# Toygether_Sch.net
KiCad netlist of a schematic drawn in Altium Designer
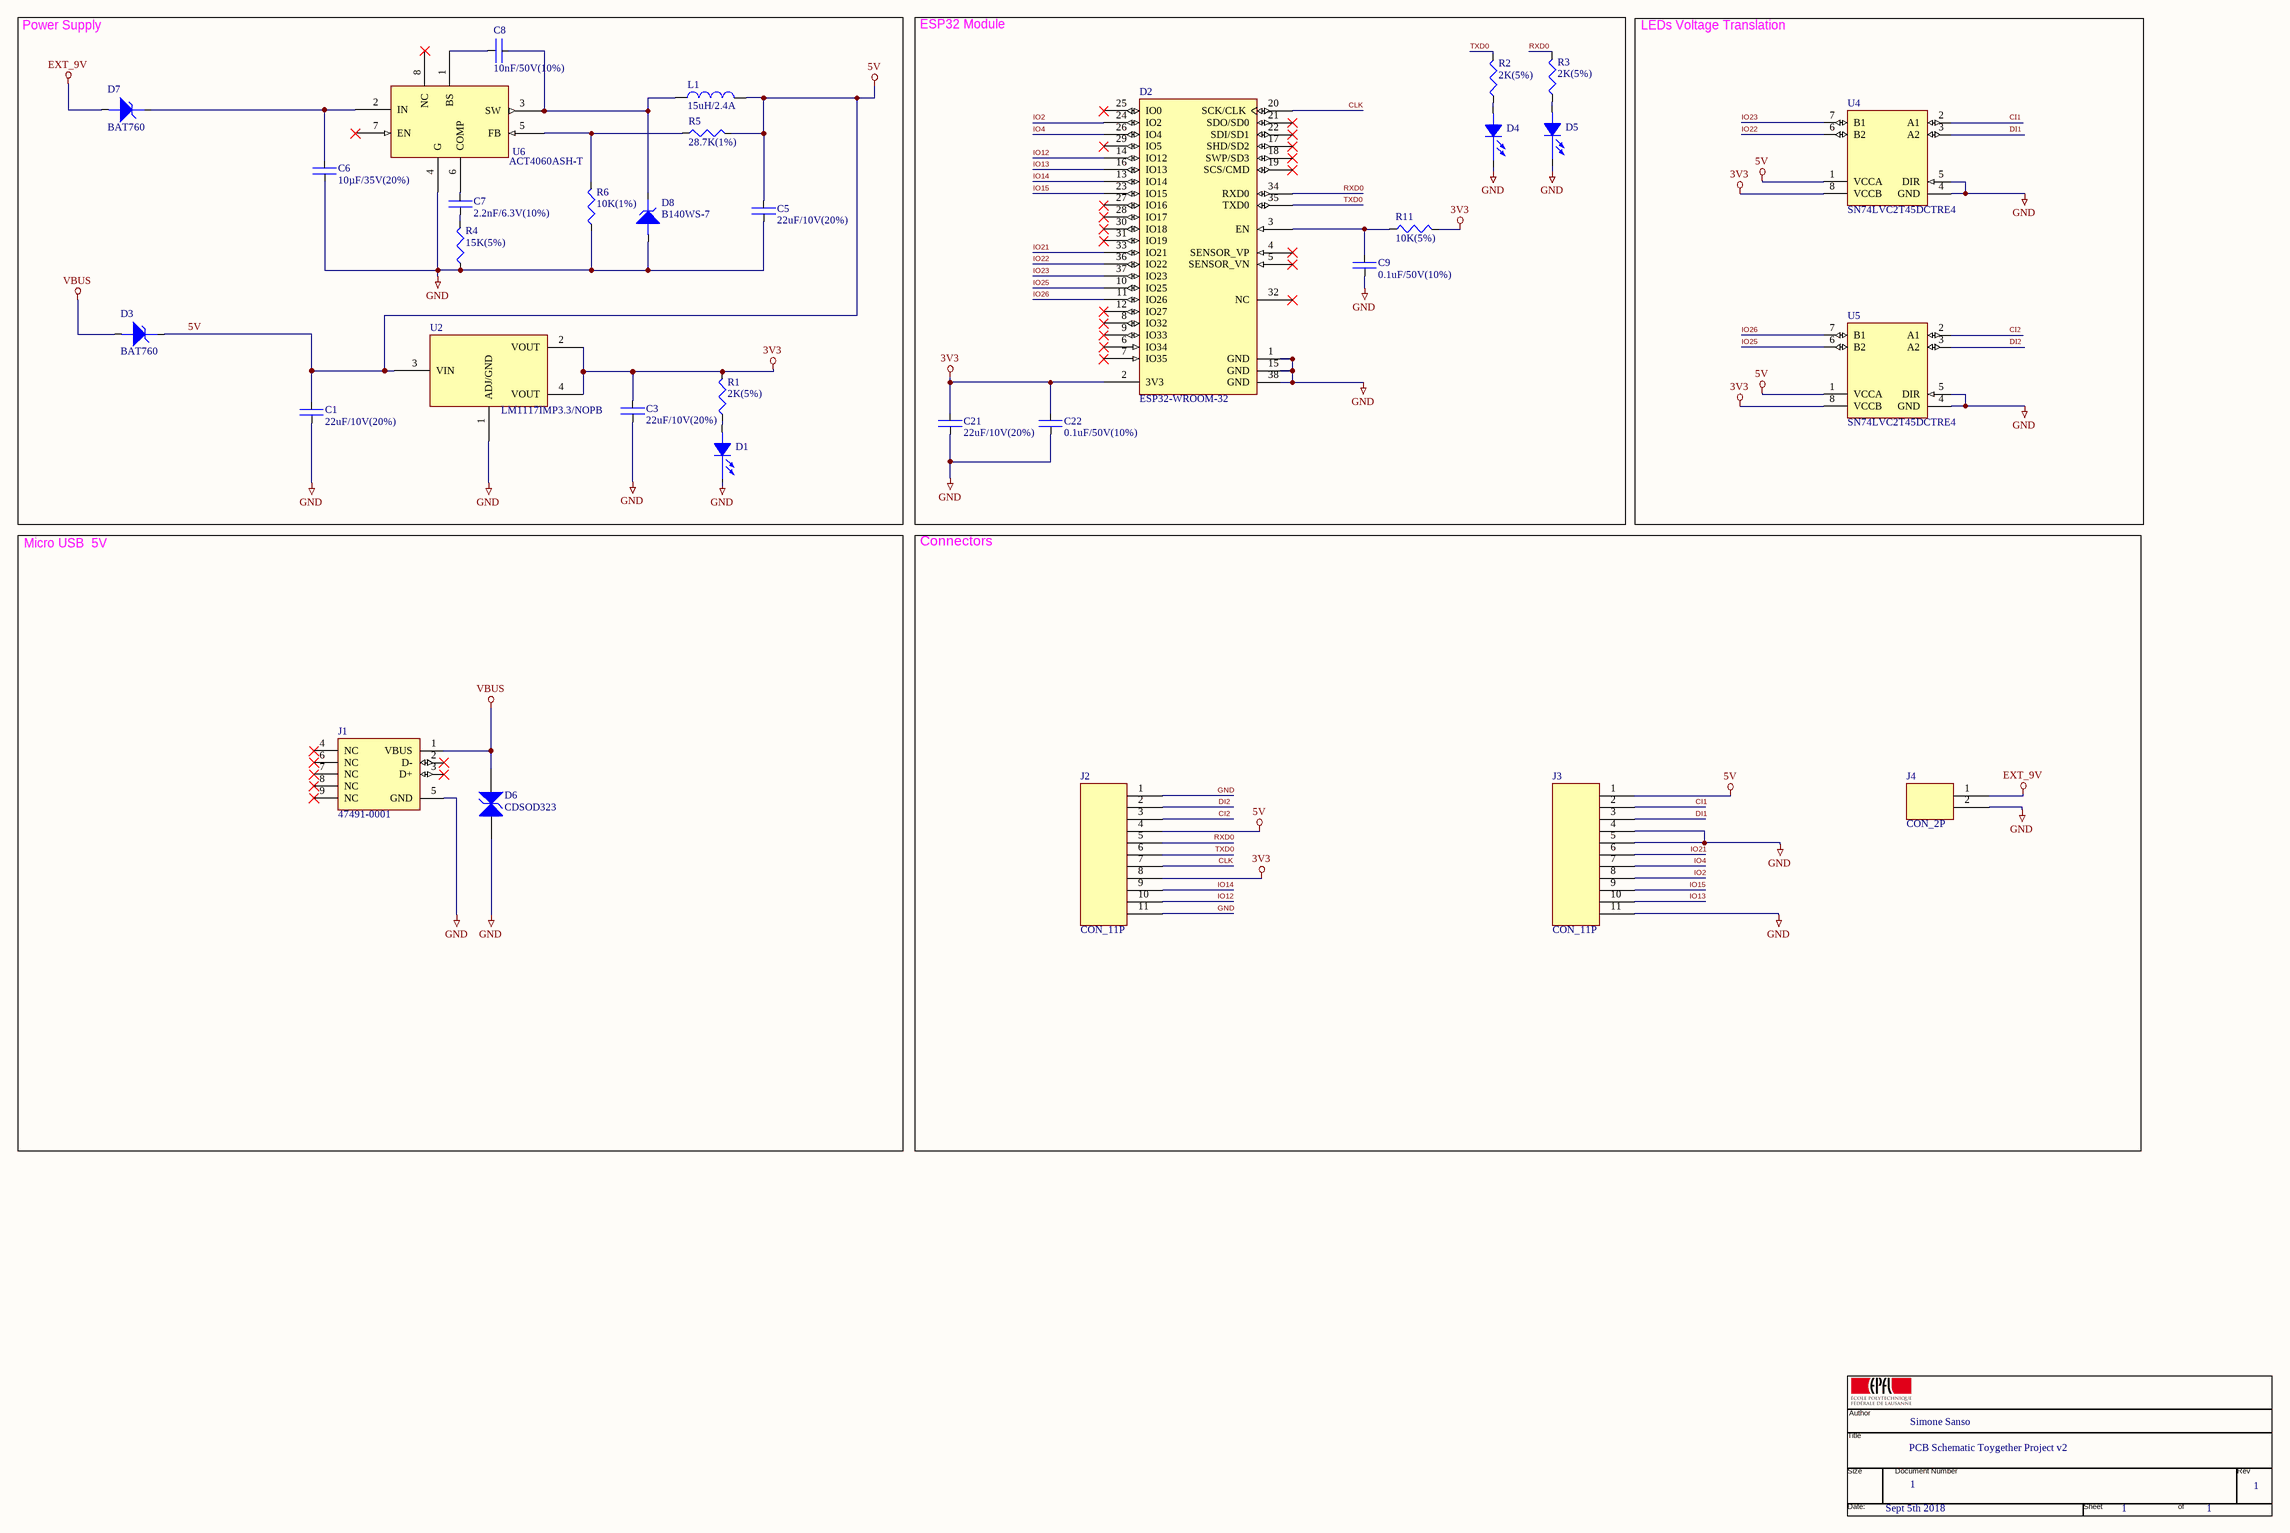
[diagram p0: Toygether_Sch.SchDoc]

(export (version "E")
  (design (tool "Eeschema 10.0.6"))
  (components
    (comp (ref "C1")
      (value "22uF/10V(20%)")
      (footprint "CAPC0603")
      (description "GRM188R61A226ME15D-22uF/10V(20%)")
      (libsource (lib "NAPaC_Schlib") (part "CAP-22uF/10V(20%)"))
    )
    (comp (ref "C3")
      (value "22uF/10V(20%)")
      (footprint "CAPC0603")
      (description "GRM188R61A226ME15D-22uF/10V(20%)")
      (libsource (lib "NAPaC_Schlib") (part "CAP-22uF/10V(20%)"))
    )
    (comp (ref "C5")
      (value "22uF/10V(20%)")
      (footprint "CAPC0603")
      (description "GRM188R61A226ME15D-22uF/10V(20%)")
      (libsource (lib "NAPaC_Schlib") (part "CAP-22uF/10V(20%)"))
    )
    (comp (ref "C6")
      (value "10µF/35V(20%)")
      (footprint "CAPC0603")
      (description "C0603C106M8PACTU")
      (libsource (lib "NAPaC_Schlib") (part "CAP-10µF/35V(20%)"))
    )
    (comp (ref "C7")
      (value "2.2nF/6.3V(10%)")
      (footprint "CAPC0603")
      (description "C0603X7R0J222K030BA")
      (libsource (lib "NAPaC_Schlib") (part "CAP-2.2nF/6.3V(10%)"))
    )
    (comp (ref "C8")
      (value "10nF/50V(10%)")
      (footprint "CAPC0603")
      (description "C1608X7R1H103K080AE")
      (libsource (lib "NAPaC_Schlib") (part "CAP-10nF/50V(10%)"))
    )
    (comp (ref "C9")
      (value "0.1uF/50V(10%)")
      (footprint "CAPC0603")
      (description "GRM188R71H104KA93D-0.1uF/50V(10%)")
      (libsource (lib "NAPaC_Schlib") (part "CAP-0.1uF/50V(10%)"))
    )
    (comp (ref "C21")
      (value "22uF/10V(20%)")
      (footprint "CAPC0603")
      (description "GRM188R61A226ME15D-22uF/10V(20%)")
      (libsource (lib "NAPaC_Schlib") (part "CAP-22uF/10V(20%)"))
    )
    (comp (ref "C22")
      (value "0.1uF/50V(10%)")
      (footprint "CAPC0603")
      (description "GRM188R71H104KA93D-0.1uF/50V(10%)")
      (libsource (lib "NAPaC_Schlib") (part "CAP-0.1uF/50V(10%)"))
    )
    (comp (ref "D1")
      (value "SML-D12U1WT86")
      (footprint "SML-D12U1WT86")
      (description "SML-D12U1WT86-2.2V-20mA")
      (libsource (lib "NAPaC_Schlib") (part "RED_LED"))
    )
    (comp (ref "D2")
      (value "ESP32-WROOM-32")
      (footprint "OLMX-ESP-WROOM-32")
      (libsource (lib "Toygether_Schlib") (part "ESP-WROOM-32"))
    )
    (comp (ref "D3")
      (value "BAT760")
      (footprint "SOD-323-SCHOTTKY_DIODE-30V/0.5A")
      (description "BAT760-7-Schottky Diodes & Rectifiers 0.5A 30V LF")
      (libsource (lib "Toygether_Schlib") (part "SCHOTTKY_DIODE-30V/0.5A"))
    )
    (comp (ref "D4")
      (value "SML-D12U1WT86")
      (footprint "SML-D12U1WT86")
      (description "SML-D12U1WT86-2.2V-20mA")
      (libsource (lib "NAPaC_Schlib") (part "RED_LED"))
    )
    (comp (ref "D5")
      (value "SML-D12U1WT86")
      (footprint "SML-D12U1WT86")
      (description "SML-D12U1WT86-2.2V-20mA")
      (libsource (lib "NAPaC_Schlib") (part "RED_LED"))
    )
    (comp (ref "D6")
      (value "CDSOD323")
      (footprint "SOD-323-SCHOTTKY_DIODE-30V/0.5A")
      (description "CDSOD323-T05LC - ESD Suppressors / TVS Diodes Bidirectional Ultra Low Cap")
      (libsource (lib "Toygether_Schlib") (part "BIDIRECTIONAL_DIODE"))
    )
    (comp (ref "D7")
      (value "BAT760")
      (footprint "SOD-323-SCHOTTKY_DIODE-30V/0.5A")
      (description "BAT760-7-Schottky Diodes & Rectifiers 0.5A 30V LF")
      (libsource (lib "Toygether_Schlib") (part "SCHOTTKY_DIODE-30V/0.5A"))
    )
    (comp (ref "D8")
      (value "B140WS-7")
      (footprint "SOD-323-SCHOTTKY_DIODE-40V/1A")
      (description "Diode Schottky 40V 1A 2-Pin SOD-323 T/R")
      (libsource (lib "NAPaC_Schlib") (part "SCHOTTKY_DIODE-40V/3A"))
    )
    (comp (ref "J1")
      (value "47491-0001")
      (footprint "USB-MICRO-B_V")
      (description "USB Connectors MICRO USB B RECPT MIDDLE MNT ASSY")
      (libsource (lib "Toygether_Schlib") (part "USB_CON8"))
    )
    (comp (ref "J2")
      (value "CON_11P")
      (footprint "PINS_HEADER-11")
      (description "11 Positions Header, Breakaway Connector 0.100\" (2.54mm) Through Hole Tin")
      (libsource (lib "Toygether_Schlib") (part "PINS_HEADER_11"))
    )
    (comp (ref "J3")
      (value "CON_11P")
      (footprint "PINS_HEADER-11")
      (description "11 Positions Header, Breakaway Connector 0.100\" (2.54mm) Through Hole Tin")
      (libsource (lib "Toygether_Schlib") (part "PINS_HEADER_11"))
    )
    (comp (ref "J4")
      (value "CON_2P")
      (footprint "PINS_ALIM-2")
      (description "2 Positions Header, Breakaway Connector 0.100\" (2.54mm) Through Hole Tin")
      (libsource (lib "NAPaC_Schlib") (part "PIN_ALIM"))
    )
    (comp (ref "L1")
      (value "15uH/2.4A")
      (footprint "NRS8040-SELF-15uH/2.4A")
      (description "NRS8040T150MJGJ")
      (libsource (lib "NAPaC_Schlib") (part "SELF-15uH/2.4A"))
    )
    (comp (ref "R1")
      (value "2K(5%)")
      (footprint "RC0402")
      (description "RC0402JR-072KL")
      (libsource (lib "NAPaC_Schlib") (part "RESISTOR-2K(5%)"))
    )
    (comp (ref "R2")
      (value "2K(5%)")
      (footprint "RC0402")
      (description "RC0402JR-072KL")
      (libsource (lib "NAPaC_Schlib") (part "RESISTOR-2K(5%)"))
    )
    (comp (ref "R3")
      (value "2K(5%)")
      (footprint "RC0402")
      (description "RC0402JR-072KL")
      (libsource (lib "NAPaC_Schlib") (part "RESISTOR-2K(5%)"))
    )
    (comp (ref "R4")
      (value "15K(5%)")
      (footprint "RC0402")
      (description "RC0402JR-0715KL")
      (libsource (lib "NAPaC_Schlib") (part "RESISTOR-15K(5%)"))
    )
    (comp (ref "R5")
      (value "28.7K(1%)")
      (footprint "RC0402")
      (description "RC0402JR-072K7L")
      (libsource (lib "NAPaC_Schlib") (part "RESISTOR-28.7K(1%)"))
    )
    (comp (ref "R6")
      (value "10K(1%)")
      (footprint "RC0402")
      (description "RC0402F103CS")
      (libsource (lib "NAPaC_Schlib") (part "RESISTOR-10K(1%)"))
    )
    (comp (ref "R11")
      (value "10K(5%)")
      (footprint "RC0402")
      (description "RC0402JR-0710KL")
      (libsource (lib "NAPaC_Schlib") (part "RESISTOR-10K(5%)"))
    )
    (comp (ref "T") (value "TITLE_BLOCK") (libsource (lib "Toygether_Schlib") (part "TITLE_BLOCK")))
    (comp (ref "U2")
      (value "LM1117IMP3.3/NOPB")
      (footprint "LM1117")
      (libsource (lib "NAPaC_Schlib") (part "LM1117-3.3"))
    )
    (comp (ref "U4")
      (value "SN74LVC2T45DCTRE4")
      (footprint "VOLTAGE_TRANSLATOR_3.3-5V")
      (description "Translation - Voltage Levels DUAL-BIT DUAL SUPPLY TRANSCEIVER")
      (libsource (lib "NAPaC_Schlib") (part "VOLTAGE_TRANSLATOR_3.3-5V"))
    )
    (comp (ref "U5")
      (value "SN74LVC2T45DCTRE4")
      (footprint "VOLTAGE_TRANSLATOR_3.3-5V")
      (description "Translation - Voltage Levels DUAL-BIT DUAL SUPPLY TRANSCEIVER")
      (libsource (lib "NAPaC_Schlib") (part "VOLTAGE_TRANSLATOR_3.3-5V"))
    )
    (comp (ref "U6")
      (value "ACT4060ASH-T")
      (footprint "SWITCHING_VOLTAGE_REGULATOR")
      (libsource (lib "NAPaC_Schlib") (part "SWITCHING_VOLTAGE_REGULATOR"))
    )
  )
  (nets
    (net (code "1") (name "/CI1") (class "Default")
      (node (ref "J3") (pin "2") (pinfunction "1_2") (pintype "passive"))
      (node (ref "U4") (pin "2") (pinfunction "A1_2") (pintype "bidirectional"))
    )
    (net (code "2") (name "/CI2") (class "Default")
      (node (ref "J2") (pin "3") (pinfunction "1_3") (pintype "passive"))
      (node (ref "U5") (pin "2") (pinfunction "A1_2") (pintype "bidirectional"))
    )
    (net (code "3") (name "/CLK") (class "Default")
      (node (ref "D2") (pin "20") (pinfunction "SCK/CLK_20") (pintype "bidirectional"))
      (node (ref "J2") (pin "7") (pinfunction "1_7") (pintype "passive"))
    )
    (net (code "4") (name "/DI1") (class "Default")
      (node (ref "J3") (pin "3") (pinfunction "1_3") (pintype "passive"))
      (node (ref "U4") (pin "3") (pinfunction "A2_3") (pintype "bidirectional"))
    )
    (net (code "5") (name "/DI2") (class "Default")
      (node (ref "J2") (pin "2") (pinfunction "1_2") (pintype "passive"))
      (node (ref "U5") (pin "3") (pinfunction "A2_3") (pintype "bidirectional"))
    )
    (net (code "6") (name "/IO2") (class "Default")
      (node (ref "D2") (pin "24") (pinfunction "IO2_24") (pintype "bidirectional"))
      (node (ref "J3") (pin "8") (pinfunction "1_8") (pintype "passive"))
    )
    (net (code "7") (name "/IO4") (class "Default")
      (node (ref "D2") (pin "26") (pinfunction "IO4_26") (pintype "bidirectional"))
      (node (ref "J3") (pin "7") (pinfunction "1_7") (pintype "passive"))
    )
    (net (code "8") (name "/IO12") (class "Default")
      (node (ref "D2") (pin "14") (pinfunction "IO12_14") (pintype "bidirectional"))
      (node (ref "J2") (pin "10") (pinfunction "1_10") (pintype "passive"))
    )
    (net (code "9") (name "/IO13") (class "Default")
      (node (ref "D2") (pin "16") (pinfunction "IO13_16") (pintype "bidirectional"))
      (node (ref "J3") (pin "10") (pinfunction "1_10") (pintype "passive"))
    )
    (net (code "10") (name "/IO14") (class "Default")
      (node (ref "D2") (pin "13") (pinfunction "IO14_13") (pintype "bidirectional"))
      (node (ref "J2") (pin "9") (pinfunction "1_9") (pintype "passive"))
    )
    (net (code "11") (name "/IO15") (class "Default")
      (node (ref "D2") (pin "23") (pinfunction "IO15_23") (pintype "bidirectional"))
      (node (ref "J3") (pin "9") (pinfunction "1_9") (pintype "passive"))
    )
    (net (code "12") (name "/IO21") (class "Default")
      (node (ref "D2") (pin "33") (pinfunction "IO21_33") (pintype "bidirectional"))
      (node (ref "J3") (pin "6") (pinfunction "1_6") (pintype "passive"))
    )
    (net (code "13") (name "/IO22") (class "Default")
      (node (ref "D2") (pin "36") (pinfunction "IO22_36") (pintype "bidirectional"))
      (node (ref "U4") (pin "6") (pinfunction "B2_6") (pintype "bidirectional"))
    )
    (net (code "14") (name "/IO23") (class "Default")
      (node (ref "D2") (pin "37") (pinfunction "IO23_37") (pintype "bidirectional"))
      (node (ref "U4") (pin "7") (pinfunction "B1_7") (pintype "bidirectional"))
    )
    (net (code "15") (name "/IO25") (class "Default")
      (node (ref "D2") (pin "10") (pinfunction "IO25_10") (pintype "bidirectional"))
      (node (ref "U5") (pin "6") (pinfunction "B2_6") (pintype "bidirectional"))
    )
    (net (code "16") (name "/IO26") (class "Default")
      (node (ref "D2") (pin "11") (pinfunction "IO26_11") (pintype "bidirectional"))
      (node (ref "U5") (pin "7") (pinfunction "B1_7") (pintype "bidirectional"))
    )
    (net (code "17") (name "/RXD0") (class "Default")
      (node (ref "D2") (pin "34") (pinfunction "RXD0_34") (pintype "bidirectional"))
      (node (ref "J2") (pin "5") (pinfunction "1_5") (pintype "passive"))
      (node (ref "R3") (pin "2") (pinfunction "2_2") (pintype "passive"))
    )
    (net (code "18") (name "/TXD0") (class "Default")
      (node (ref "D2") (pin "35") (pinfunction "TXD0_35") (pintype "bidirectional"))
      (node (ref "J2") (pin "6") (pinfunction "1_6") (pintype "passive"))
      (node (ref "R2") (pin "2") (pinfunction "2_2") (pintype "passive"))
    )
    (net (code "19") (name "3V3") (class "Default")
      (node (ref "C21") (pin "2") (pinfunction "2_2") (pintype "passive"))
      (node (ref "C22") (pin "2") (pinfunction "2_2") (pintype "passive"))
      (node (ref "C3") (pin "2") (pinfunction "2_2") (pintype "passive"))
      (node (ref "D2") (pin "2") (pinfunction "3V3_2") (pintype "power_in"))
      (node (ref "J2") (pin "8") (pinfunction "1_8") (pintype "passive"))
      (node (ref "R1") (pin "2") (pinfunction "2_2") (pintype "passive"))
      (node (ref "R11") (pin "2") (pinfunction "2_2") (pintype "passive"))
      (node (ref "U2") (pin "2") (pinfunction "VOUT_2") (pintype "power_in"))
      (node (ref "U2") (pin "4") (pinfunction "VOUT_4") (pintype "power_in"))
      (node (ref "U4") (pin "8") (pinfunction "VCCB_8") (pintype "power_in"))
      (node (ref "U5") (pin "8") (pinfunction "VCCB_8") (pintype "power_in"))
    )
    (net (code "20") (name "5V") (class "Default")
      (node (ref "C1") (pin "2") (pinfunction "2_2") (pintype "passive"))
      (node (ref "C5") (pin "2") (pinfunction "2_2") (pintype "passive"))
      (node (ref "D3") (pin "2") (pinfunction "K_2") (pintype "passive"))
      (node (ref "J2") (pin "4") (pinfunction "1_4") (pintype "passive"))
      (node (ref "J3") (pin "1") (pinfunction "1_1") (pintype "passive"))
      (node (ref "L1") (pin "2") (pinfunction "2_2") (pintype "passive"))
      (node (ref "R5") (pin "2") (pinfunction "2_2") (pintype "passive"))
      (node (ref "U2") (pin "3") (pinfunction "VIN_3") (pintype "power_in"))
      (node (ref "U4") (pin "1") (pinfunction "VCCA_1") (pintype "power_in"))
      (node (ref "U5") (pin "1") (pinfunction "VCCA_1") (pintype "power_in"))
    )
    (net (code "21") (name "EXT_9V") (class "Default")
      (node (ref "D7") (pin "1") (pinfunction "A_1") (pintype "passive"))
      (node (ref "J4") (pin "1") (pinfunction "VIN_1") (pintype "power_in"))
    )
    (net (code "22") (name "GND") (class "Default")
      (node (ref "C1") (pin "1") (pinfunction "1_1") (pintype "passive"))
      (node (ref "C21") (pin "1") (pinfunction "1_1") (pintype "passive"))
      (node (ref "C22") (pin "1") (pinfunction "1_1") (pintype "passive"))
      (node (ref "C3") (pin "1") (pinfunction "1_1") (pintype "passive"))
      (node (ref "C5") (pin "1") (pinfunction "1_1") (pintype "passive"))
      (node (ref "C6") (pin "1") (pinfunction "1_1") (pintype "passive"))
      (node (ref "C9") (pin "1") (pinfunction "1_1") (pintype "passive"))
      (node (ref "D1") (pin "2") (pinfunction "2_2") (pintype "passive"))
      (node (ref "D2") (pin "1") (pinfunction "GND_1") (pintype "power_in"))
      (node (ref "D2") (pin "15") (pinfunction "GND_15") (pintype "power_in"))
      (node (ref "D2") (pin "38") (pinfunction "GND_38") (pintype "power_in"))
      (node (ref "D4") (pin "2") (pinfunction "2_2") (pintype "passive"))
      (node (ref "D5") (pin "2") (pinfunction "2_2") (pintype "passive"))
      (node (ref "D6") (pin "1") (pinfunction "C_1") (pintype "passive"))
      (node (ref "D8") (pin "1") (pinfunction "A_1") (pintype "passive"))
      (node (ref "J1") (pin "5") (pinfunction "GND_5") (pintype "power_in"))
      (node (ref "J2") (pin "1") (pinfunction "1_1") (pintype "passive"))
      (node (ref "J2") (pin "11") (pinfunction "1_11") (pintype "passive"))
      (node (ref "J3") (pin "11") (pinfunction "1_11") (pintype "passive"))
      (node (ref "J3") (pin "4") (pinfunction "1_4") (pintype "passive"))
      (node (ref "J3") (pin "5") (pinfunction "1_5") (pintype "passive"))
      (node (ref "J4") (pin "2") (pinfunction "GND_2") (pintype "passive"))
      (node (ref "R4") (pin "1") (pinfunction "1_1") (pintype "passive"))
      (node (ref "R6") (pin "1") (pinfunction "1_1") (pintype "passive"))
      (node (ref "U2") (pin "1") (pinfunction "ADJ/GND_1") (pintype "passive"))
      (node (ref "U4") (pin "4") (pinfunction "GND_4") (pintype "power_in"))
      (node (ref "U4") (pin "5") (pinfunction "DIR_5") (pintype "input"))
      (node (ref "U5") (pin "4") (pinfunction "GND_4") (pintype "power_in"))
      (node (ref "U5") (pin "5") (pinfunction "DIR_5") (pintype "input"))
      (node (ref "U6") (pin "4") (pinfunction "G_4") (pintype "power_in"))
    )
    (net (code "23") (name "Net-(C7-Pad1)") (class "Default")
      (node (ref "C7") (pin "1") (pinfunction "1_1") (pintype "passive"))
      (node (ref "R4") (pin "2") (pinfunction "2_2") (pintype "passive"))
    )
    (net (code "24") (name "Net-(D1-Pad1)") (class "Default")
      (node (ref "D1") (pin "1") (pinfunction "1_1") (pintype "passive"))
      (node (ref "R1") (pin "1") (pinfunction "1_1") (pintype "passive"))
    )
    (net (code "25") (name "Net-(D2-EN)") (class "Default")
      (node (ref "C9") (pin "2") (pinfunction "2_2") (pintype "passive"))
      (node (ref "D2") (pin "3") (pinfunction "EN_3") (pintype "input"))
      (node (ref "R11") (pin "1") (pinfunction "1_1") (pintype "passive"))
    )
    (net (code "26") (name "Net-(D4-Pad1)") (class "Default")
      (node (ref "D4") (pin "1") (pinfunction "1_1") (pintype "passive"))
      (node (ref "R2") (pin "1") (pinfunction "1_1") (pintype "passive"))
    )
    (net (code "27") (name "Net-(D5-Pad1)") (class "Default")
      (node (ref "D5") (pin "1") (pinfunction "1_1") (pintype "passive"))
      (node (ref "R3") (pin "1") (pinfunction "1_1") (pintype "passive"))
    )
    (net (code "28") (name "Net-(D7-K)") (class "Default")
      (node (ref "C6") (pin "2") (pinfunction "2_2") (pintype "passive"))
      (node (ref "D7") (pin "2") (pinfunction "K_2") (pintype "passive"))
      (node (ref "U6") (pin "2") (pinfunction "IN_2") (pintype "power_in"))
    )
    (net (code "29") (name "Net-(D8-K)") (class "Default")
      (node (ref "C8") (pin "2") (pinfunction "2_2") (pintype "passive"))
      (node (ref "D8") (pin "2") (pinfunction "K_2") (pintype "passive"))
      (node (ref "L1") (pin "1") (pinfunction "1_1") (pintype "passive"))
      (node (ref "U6") (pin "3") (pinfunction "SW_3") (pintype "output"))
    )
    (net (code "30") (name "Net-(U6-BS)") (class "Default")
      (node (ref "C8") (pin "1") (pinfunction "1_1") (pintype "passive"))
      (node (ref "U6") (pin "1") (pinfunction "BS_1") (pintype "passive"))
    )
    (net (code "31") (name "Net-(U6-COMP)") (class "Default")
      (node (ref "C7") (pin "2") (pinfunction "2_2") (pintype "passive"))
      (node (ref "U6") (pin "6") (pinfunction "COMP_6") (pintype "passive"))
    )
    (net (code "32") (name "Net-(U6-FB)") (class "Default")
      (node (ref "R5") (pin "1") (pinfunction "1_1") (pintype "passive"))
      (node (ref "R6") (pin "2") (pinfunction "2_2") (pintype "passive"))
      (node (ref "U6") (pin "5") (pinfunction "FB_5") (pintype "input"))
    )
    (net (code "33") (name "VBUS") (class "Default")
      (node (ref "D3") (pin "1") (pinfunction "A_1") (pintype "passive"))
      (node (ref "D6") (pin "2") (pinfunction "C_2") (pintype "passive"))
      (node (ref "J1") (pin "1") (pinfunction "VBUS_1") (pintype "power_in"))
    )
    (net (code "34") (name "unconnected-(D2-IO0-Pad25)") (class "Default")
      (node (ref "D2") (pin "25") (pinfunction "IO0_25") (pintype "bidirectional+no_connect"))
    )
    (net (code "35") (name "unconnected-(D2-IO5-Pad29)") (class "Default")
      (node (ref "D2") (pin "29") (pinfunction "IO5_29") (pintype "bidirectional+no_connect"))
    )
    (net (code "36") (name "unconnected-(D2-IO16-Pad27)") (class "Default")
      (node (ref "D2") (pin "27") (pinfunction "IO16_27") (pintype "bidirectional+no_connect"))
    )
    (net (code "37") (name "unconnected-(D2-IO17-Pad28)") (class "Default")
      (node (ref "D2") (pin "28") (pinfunction "IO17_28") (pintype "bidirectional+no_connect"))
    )
    (net (code "38") (name "unconnected-(D2-IO18-Pad30)") (class "Default")
      (node (ref "D2") (pin "30") (pinfunction "IO18_30") (pintype "bidirectional+no_connect"))
    )
    (net (code "39") (name "unconnected-(D2-IO19-Pad31)") (class "Default")
      (node (ref "D2") (pin "31") (pinfunction "IO19_31") (pintype "bidirectional+no_connect"))
    )
    (net (code "40") (name "unconnected-(D2-IO27-Pad12)") (class "Default")
      (node (ref "D2") (pin "12") (pinfunction "IO27_12") (pintype "bidirectional+no_connect"))
    )
    (net (code "41") (name "unconnected-(D2-IO32-Pad8)") (class "Default")
      (node (ref "D2") (pin "8") (pinfunction "IO32_8") (pintype "bidirectional+no_connect"))
    )
    (net (code "42") (name "unconnected-(D2-IO33-Pad9)") (class "Default")
      (node (ref "D2") (pin "9") (pinfunction "IO33_9") (pintype "bidirectional+no_connect"))
    )
    (net (code "43") (name "unconnected-(D2-IO34-Pad6)") (class "Default")
      (node (ref "D2") (pin "6") (pinfunction "IO34_6") (pintype "input+no_connect"))
    )
    (net (code "44") (name "unconnected-(D2-IO35-Pad7)") (class "Default")
      (node (ref "D2") (pin "7") (pinfunction "IO35_7") (pintype "input+no_connect"))
    )
    (net (code "45") (name "unconnected-(D2-NC-Pad32)") (class "Default")
      (node (ref "D2") (pin "32") (pinfunction "NC_32") (pintype "passive+no_connect"))
    )
    (net (code "46") (name "unconnected-(D2-SCS{slash}CMD-Pad19)") (class "Default")
      (node (ref "D2") (pin "19") (pinfunction "SCS/CMD_19") (pintype "bidirectional+no_connect"))
    )
    (net (code "47") (name "unconnected-(D2-SDI{slash}SD1-Pad22)") (class "Default")
      (node (ref "D2") (pin "22") (pinfunction "SDI/SD1_22") (pintype "bidirectional+no_connect"))
    )
    (net (code "48") (name "unconnected-(D2-SDO{slash}SD0-Pad21)") (class "Default")
      (node (ref "D2") (pin "21") (pinfunction "SDO/SD0_21") (pintype "bidirectional+no_connect"))
    )
    (net (code "49") (name "unconnected-(D2-SENSOR_VN-Pad5)") (class "Default")
      (node (ref "D2") (pin "5") (pinfunction "SENSOR_VN_5") (pintype "input+no_connect"))
    )
    (net (code "50") (name "unconnected-(D2-SENSOR_VP-Pad4)") (class "Default")
      (node (ref "D2") (pin "4") (pinfunction "SENSOR_VP_4") (pintype "input+no_connect"))
    )
    (net (code "51") (name "unconnected-(D2-SHD{slash}SD2-Pad17)") (class "Default")
      (node (ref "D2") (pin "17") (pinfunction "SHD/SD2_17") (pintype "bidirectional+no_connect"))
    )
    (net (code "52") (name "unconnected-(D2-SWP{slash}SD3-Pad18)") (class "Default")
      (node (ref "D2") (pin "18") (pinfunction "SWP/SD3_18") (pintype "bidirectional+no_connect"))
    )
    (net (code "53") (name "unconnected-(J1-D+-Pad3)") (class "Default")
      (node (ref "J1") (pin "3") (pinfunction "D+_3") (pintype "bidirectional+no_connect"))
    )
    (net (code "54") (name "unconnected-(J1-D--Pad2)") (class "Default")
      (node (ref "J1") (pin "2") (pinfunction "D-_2") (pintype "bidirectional+no_connect"))
    )
    (net (code "55") (name "unconnected-(J1-NC-Pad4)") (class "Default")
      (node (ref "J1") (pin "4") (pinfunction "NC_4") (pintype "passive+no_connect"))
    )
    (net (code "56") (name "unconnected-(J1-NC-Pad6)") (class "Default")
      (node (ref "J1") (pin "6") (pinfunction "NC_6") (pintype "passive+no_connect"))
    )
    (net (code "57") (name "unconnected-(J1-NC-Pad7)") (class "Default")
      (node (ref "J1") (pin "7") (pinfunction "NC_7") (pintype "passive+no_connect"))
    )
    (net (code "58") (name "unconnected-(J1-NC-Pad8)") (class "Default")
      (node (ref "J1") (pin "8") (pinfunction "NC_8") (pintype "passive+no_connect"))
    )
    (net (code "59") (name "unconnected-(J1-NC-Pad9)") (class "Default")
      (node (ref "J1") (pin "9") (pinfunction "NC_9") (pintype "passive+no_connect"))
    )
    (net (code "60") (name "unconnected-(U6-EN-Pad7)") (class "Default")
      (node (ref "U6") (pin "7") (pinfunction "EN_7") (pintype "input+no_connect"))
    )
    (net (code "61") (name "unconnected-(U6-NC-Pad8)") (class "Default")
      (node (ref "U6") (pin "8") (pinfunction "NC_8") (pintype "passive+no_connect"))
    )
  )
)
